# a_blue_tooth_control_security_light.net
KiCad netlist of a schematic drawn in EasyEDA
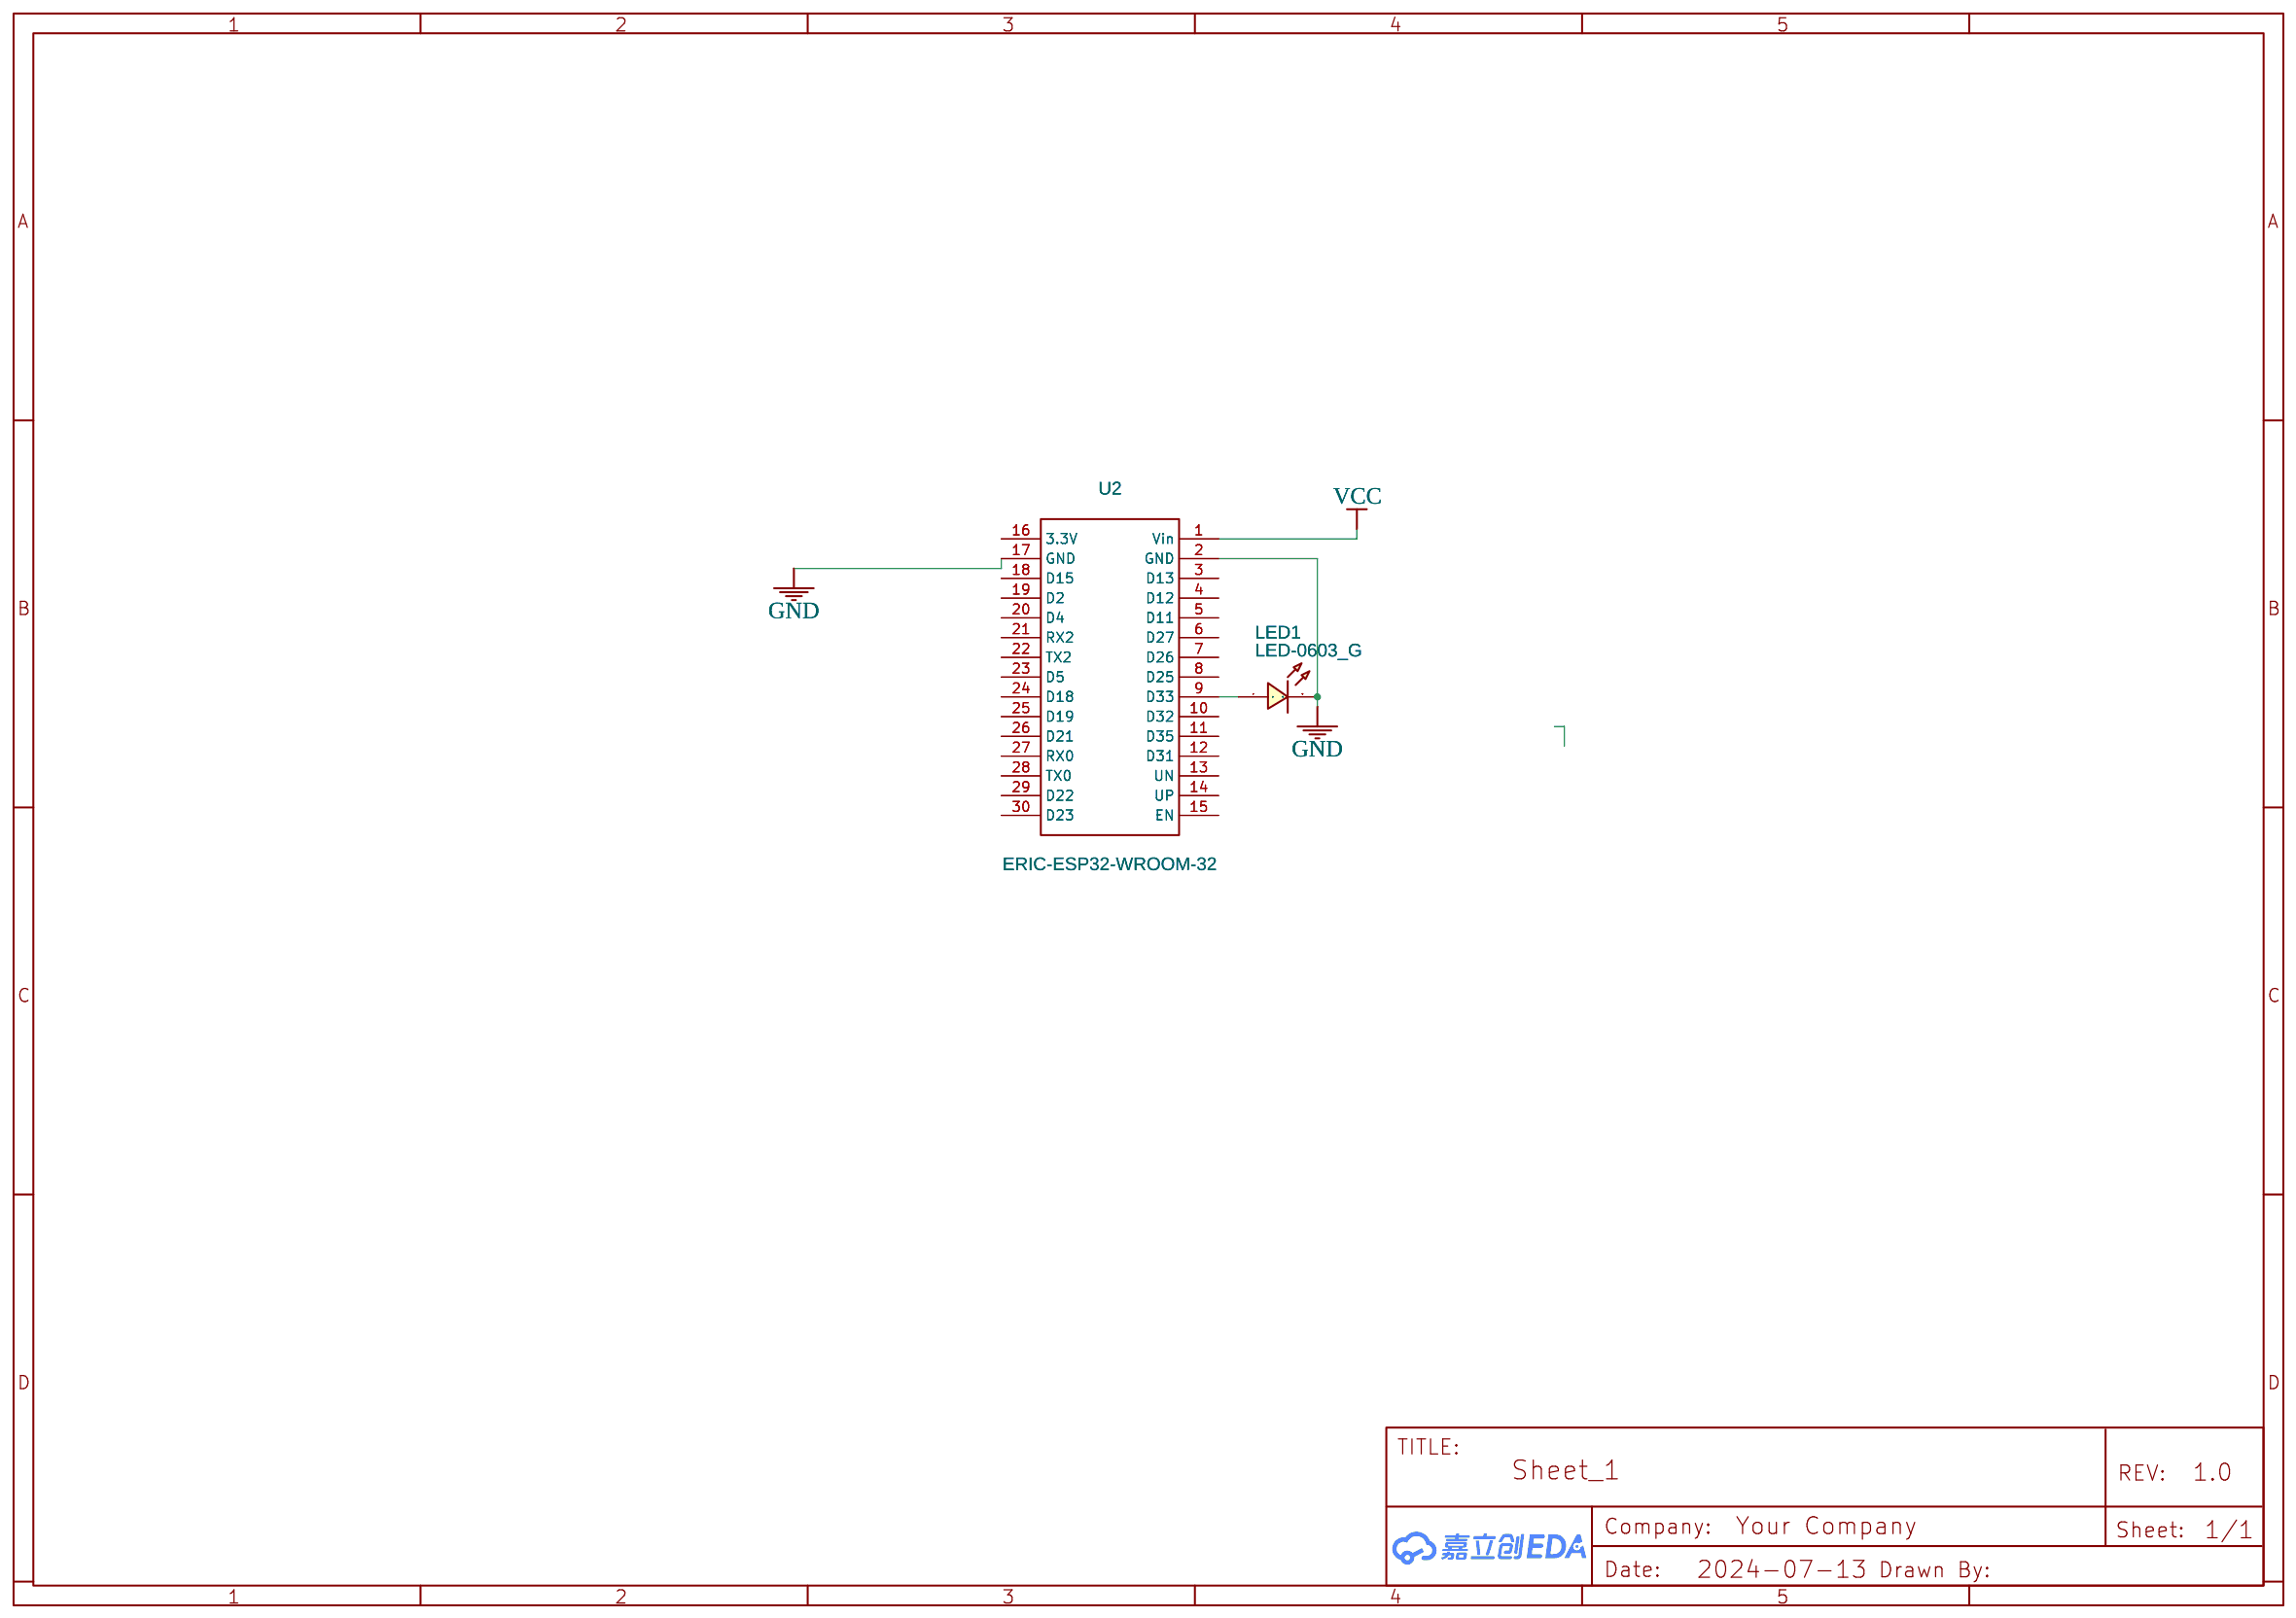
[diagram p0: schematic sheet]

(export (version "E")
  (design (tool "Eeschema 10.0.6"))
  (components
    (comp (ref "LED1")
      (value "LED-0603_G")
      (fields
        (field (name "BOM_Manufacturer Part") "19-217/GHC-YR1S2/3T")
        (field (name "BOM_Supplier Part") "C72043")
      )
      (libsource (lib "") (part "LED-0603_G"))
    )
    (comp (ref "U2")
      (value "ERIC-ESP32-WROOM-32")
      (fields (field (name "BOM_Supplier Part") "ESP32-WROOM-32"))
      (libsource (lib "") (part "ESP32-WROOM-32"))
    )
  )
  (nets
    (net (code "1") (name "GND") (class "Default")
      (node (ref "LED1") (pin "2") (pinfunction "2_2") (pintype "unspecified"))
      (node (ref "U2") (pin "17") (pinfunction "GND_17") (pintype "unspecified"))
      (node (ref "U2") (pin "2") (pinfunction "GND_2") (pintype "unspecified"))
    )
    (net (code "2") (name "Net-(U2-D33)") (class "Default")
      (node (ref "LED1") (pin "1") (pinfunction "1_1") (pintype "unspecified"))
      (node (ref "U2") (pin "9") (pinfunction "D33_9") (pintype "unspecified"))
    )
    (net (code "3") (name "VCC") (class "Default")
      (node (ref "U2") (pin "1") (pinfunction "Vin_1") (pintype "unspecified"))
    )
    (net (code "4") (name "unconnected-(U2-3.3V-Pad16)") (class "Default")
      (node (ref "U2") (pin "16") (pinfunction "3.3V_16") (pintype "unspecified"))
    )
    (net (code "5") (name "unconnected-(U2-D2-Pad19)") (class "Default")
      (node (ref "U2") (pin "19") (pinfunction "D2_19") (pintype "unspecified"))
    )
    (net (code "6") (name "unconnected-(U2-D4-Pad20)") (class "Default")
      (node (ref "U2") (pin "20") (pinfunction "D4_20") (pintype "unspecified"))
    )
    (net (code "7") (name "unconnected-(U2-D5-Pad23)") (class "Default")
      (node (ref "U2") (pin "23") (pinfunction "D5_23") (pintype "unspecified"))
    )
    (net (code "8") (name "unconnected-(U2-D11-Pad5)") (class "Default")
      (node (ref "U2") (pin "5") (pinfunction "D11_5") (pintype "unspecified"))
    )
    (net (code "9") (name "unconnected-(U2-D12-Pad4)") (class "Default")
      (node (ref "U2") (pin "4") (pinfunction "D12_4") (pintype "unspecified"))
    )
    (net (code "10") (name "unconnected-(U2-D13-Pad3)") (class "Default")
      (node (ref "U2") (pin "3") (pinfunction "D13_3") (pintype "unspecified"))
    )
    (net (code "11") (name "unconnected-(U2-D15-Pad18)") (class "Default")
      (node (ref "U2") (pin "18") (pinfunction "D15_18") (pintype "unspecified"))
    )
    (net (code "12") (name "unconnected-(U2-D18-Pad24)") (class "Default")
      (node (ref "U2") (pin "24") (pinfunction "D18_24") (pintype "unspecified"))
    )
    (net (code "13") (name "unconnected-(U2-D19-Pad25)") (class "Default")
      (node (ref "U2") (pin "25") (pinfunction "D19_25") (pintype "unspecified"))
    )
    (net (code "14") (name "unconnected-(U2-D21-Pad26)") (class "Default")
      (node (ref "U2") (pin "26") (pinfunction "D21_26") (pintype "unspecified"))
    )
    (net (code "15") (name "unconnected-(U2-D22-Pad29)") (class "Default")
      (node (ref "U2") (pin "29") (pinfunction "D22_29") (pintype "unspecified"))
    )
    (net (code "16") (name "unconnected-(U2-D23-Pad30)") (class "Default")
      (node (ref "U2") (pin "30") (pinfunction "D23_30") (pintype "unspecified"))
    )
    (net (code "17") (name "unconnected-(U2-D25-Pad8)") (class "Default")
      (node (ref "U2") (pin "8") (pinfunction "D25_8") (pintype "unspecified"))
    )
    (net (code "18") (name "unconnected-(U2-D26-Pad7)") (class "Default")
      (node (ref "U2") (pin "7") (pinfunction "D26_7") (pintype "unspecified"))
    )
    (net (code "19") (name "unconnected-(U2-D27-Pad6)") (class "Default")
      (node (ref "U2") (pin "6") (pinfunction "D27_6") (pintype "unspecified"))
    )
    (net (code "20") (name "unconnected-(U2-D31-Pad12)") (class "Default")
      (node (ref "U2") (pin "12") (pinfunction "D31_12") (pintype "unspecified"))
    )
    (net (code "21") (name "unconnected-(U2-D32-Pad10)") (class "Default")
      (node (ref "U2") (pin "10") (pinfunction "D32_10") (pintype "unspecified"))
    )
    (net (code "22") (name "unconnected-(U2-D35-Pad11)") (class "Default")
      (node (ref "U2") (pin "11") (pinfunction "D35_11") (pintype "unspecified"))
    )
    (net (code "23") (name "unconnected-(U2-EN-Pad15)") (class "Default")
      (node (ref "U2") (pin "15") (pinfunction "EN_15") (pintype "unspecified"))
    )
    (net (code "24") (name "unconnected-(U2-RX0-Pad27)") (class "Default")
      (node (ref "U2") (pin "27") (pinfunction "RX0_27") (pintype "unspecified"))
    )
    (net (code "25") (name "unconnected-(U2-RX2-Pad21)") (class "Default")
      (node (ref "U2") (pin "21") (pinfunction "RX2_21") (pintype "unspecified"))
    )
    (net (code "26") (name "unconnected-(U2-TX0-Pad28)") (class "Default")
      (node (ref "U2") (pin "28") (pinfunction "TX0_28") (pintype "unspecified"))
    )
    (net (code "27") (name "unconnected-(U2-TX2-Pad22)") (class "Default")
      (node (ref "U2") (pin "22") (pinfunction "TX2_22") (pintype "unspecified"))
    )
    (net (code "28") (name "unconnected-(U2-UN-Pad13)") (class "Default")
      (node (ref "U2") (pin "13") (pinfunction "UN_13") (pintype "unspecified"))
    )
    (net (code "29") (name "unconnected-(U2-UP-Pad14)") (class "Default")
      (node (ref "U2") (pin "14") (pinfunction "UP_14") (pintype "unspecified"))
    )
  )
)
